# NU-Smarticles.net
KiCad netlist of a schematic drawn in EAGLE
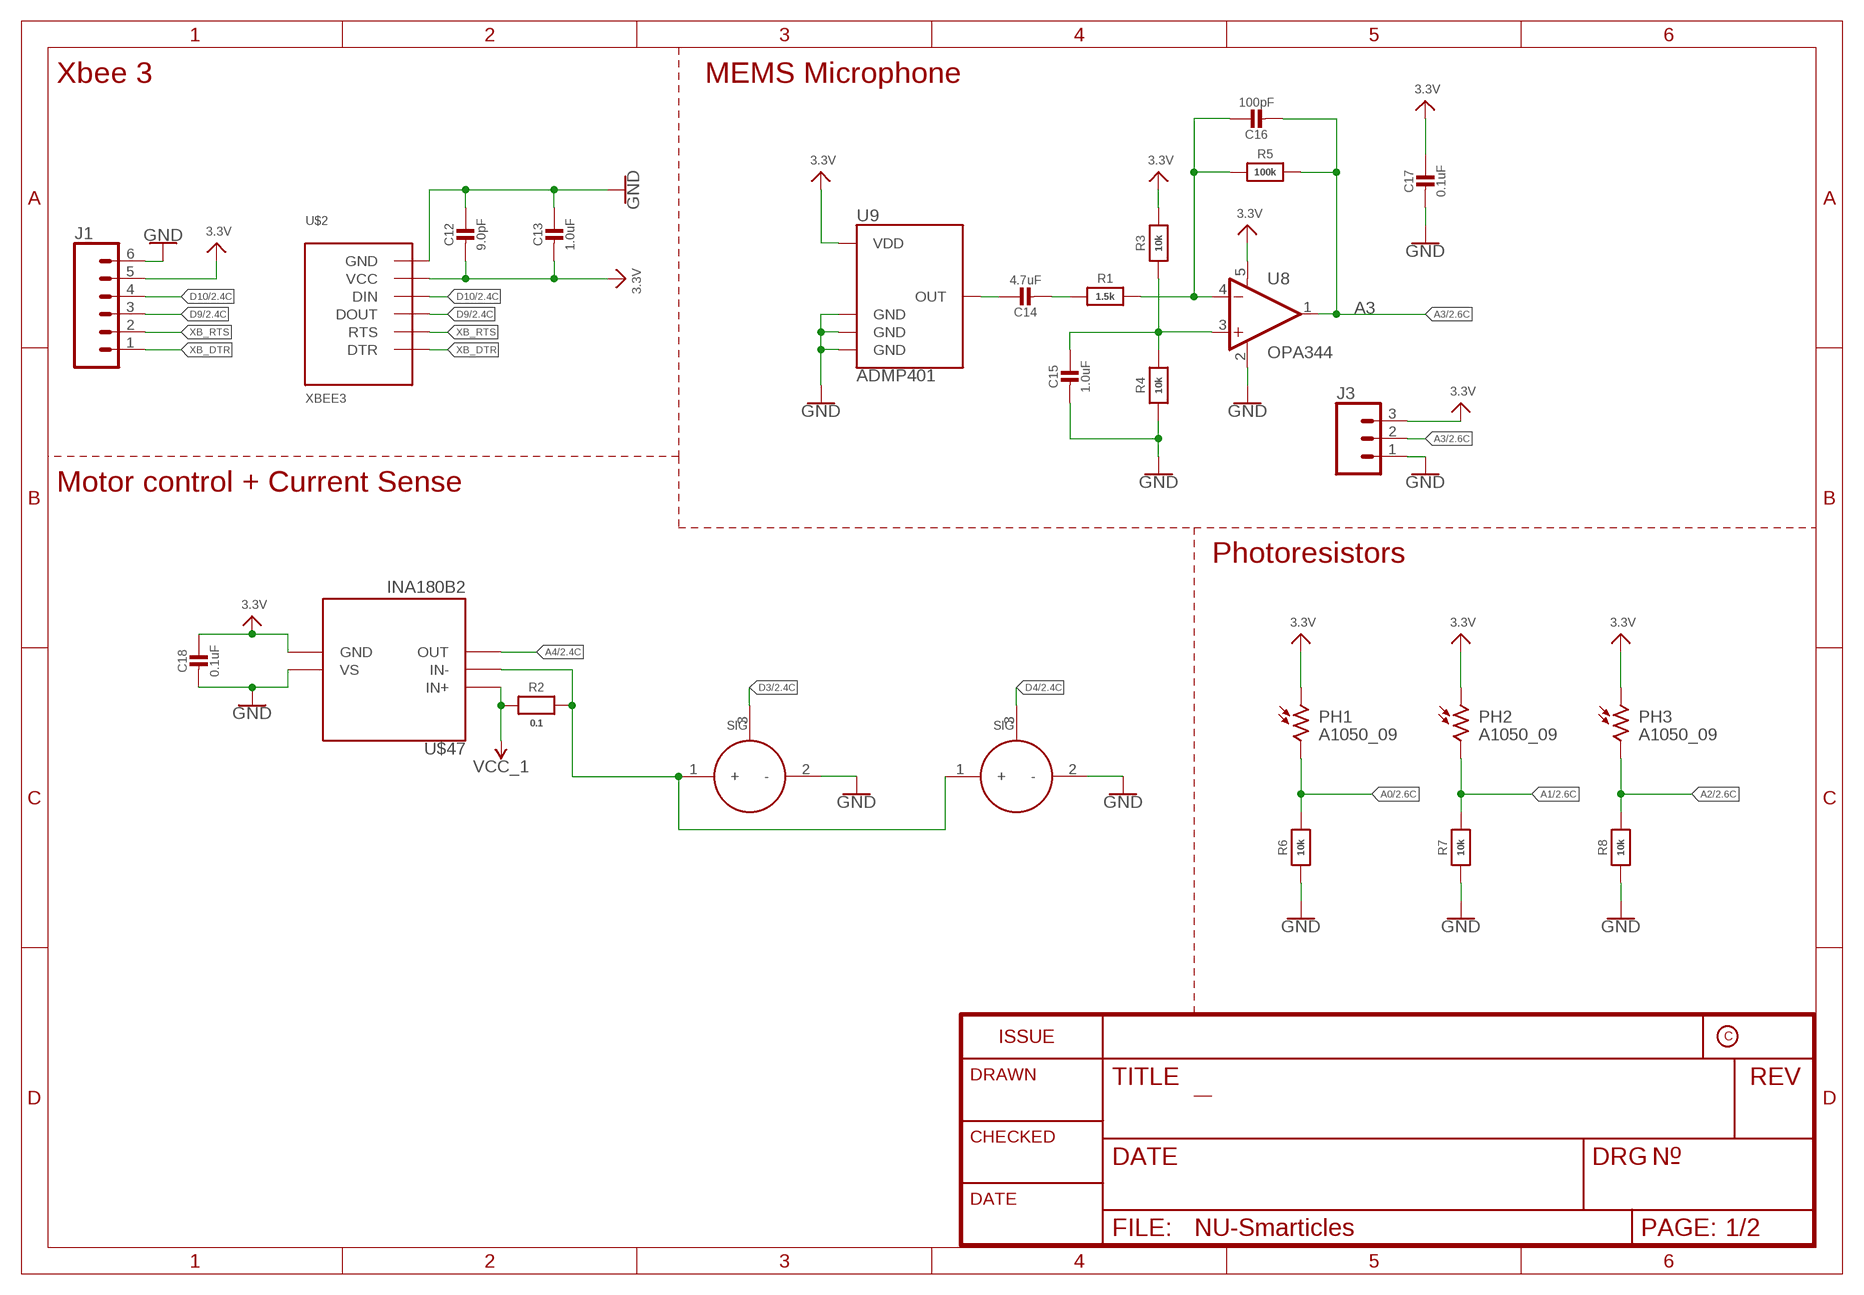
[diagram p0: schematic, sheet 1]
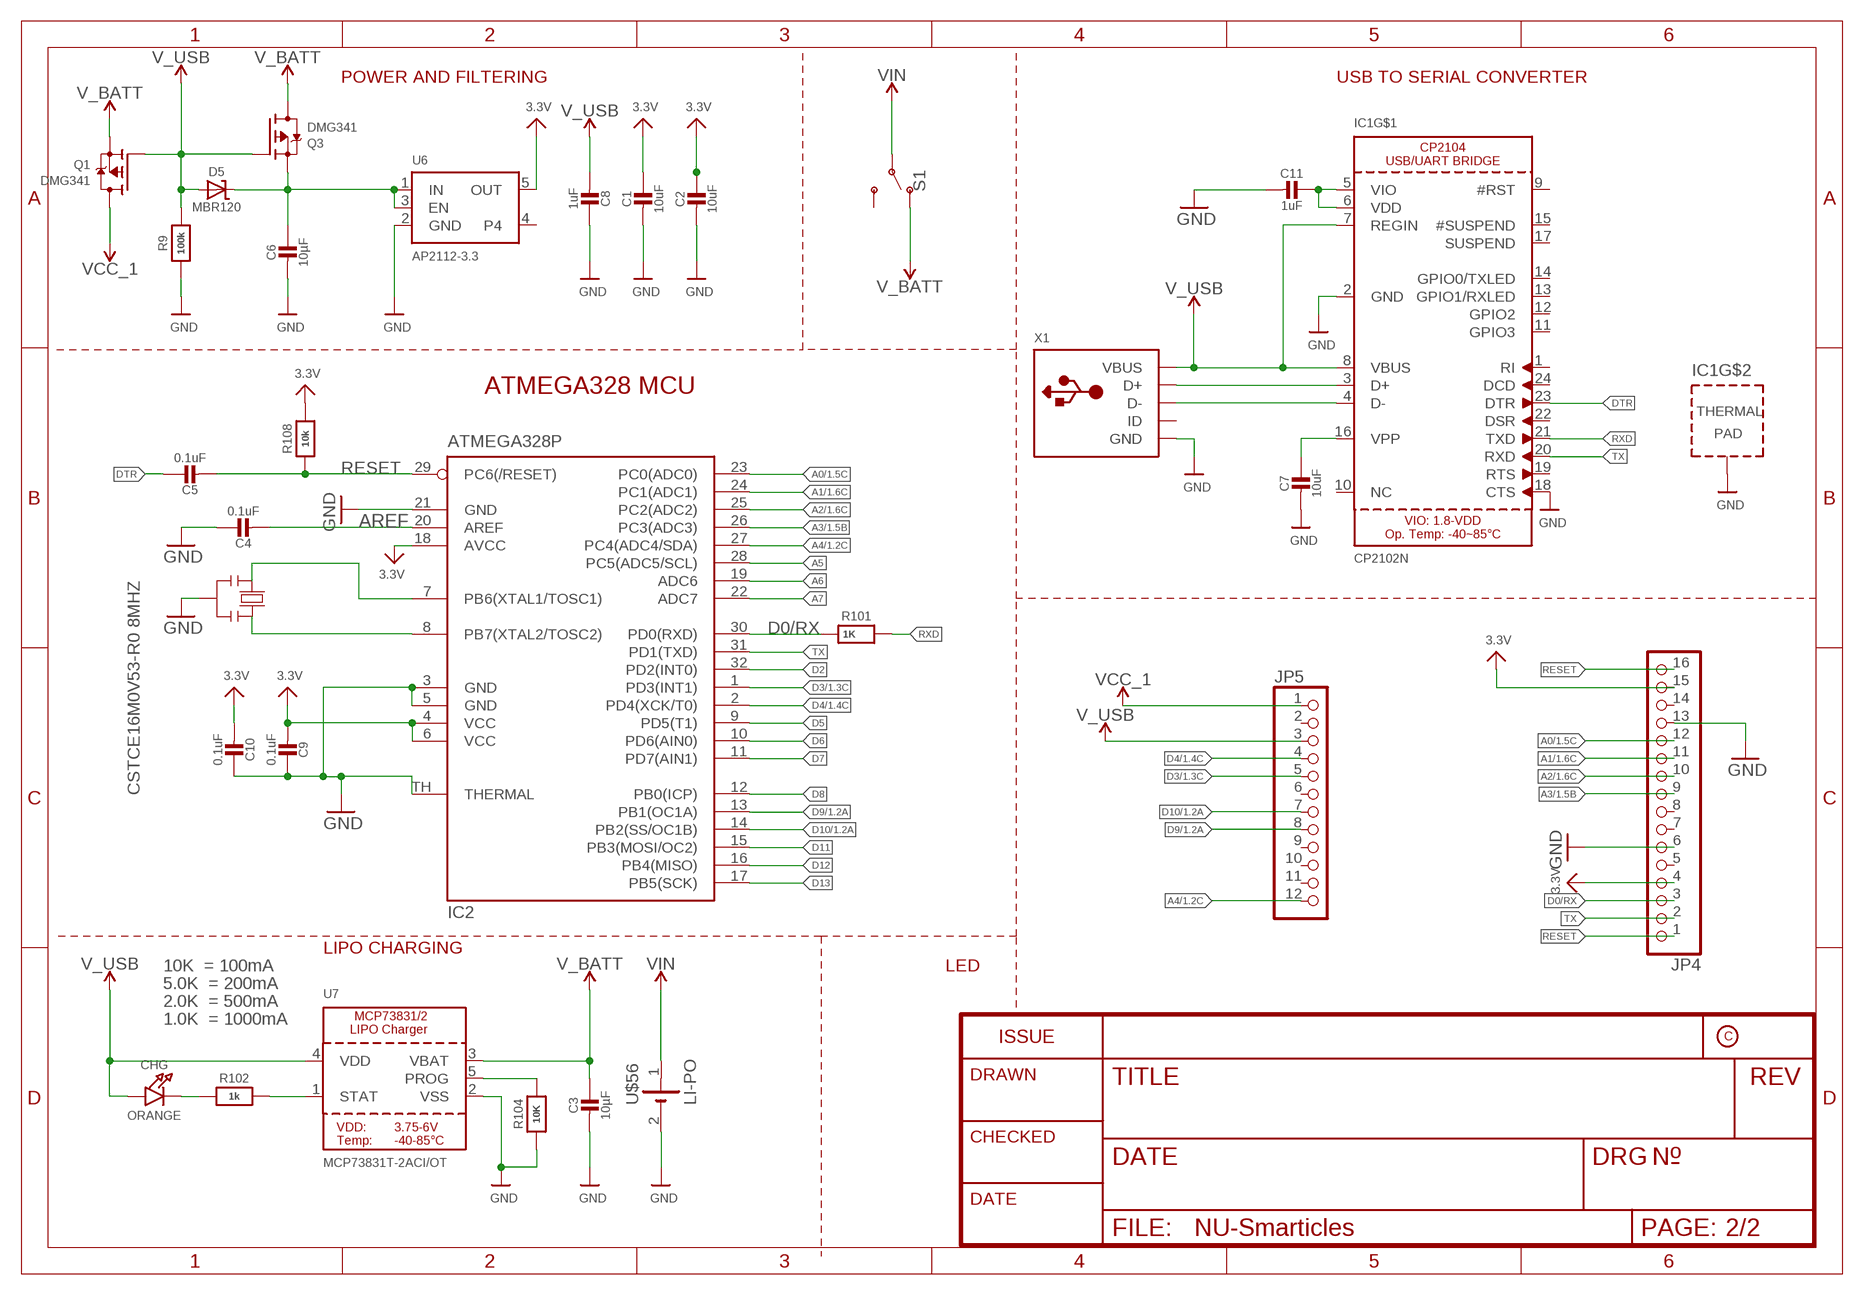
[diagram p1: schematic, sheet 2]

(export (version "E")
  (design (tool "Eeschema 10.0.6"))
  (components
    (comp (ref "C1")
      (value "10uF")
      (footprint "eagle-import:_0402MP")
      (libsource (lib "eagle-import") (part "CAP_CERAMIC_0402MP"))
    )
    (comp (ref "C2")
      (value "10uF")
      (footprint "eagle-import:_0402MP")
      (libsource (lib "eagle-import") (part "CAP_CERAMIC_0402MP"))
    )
    (comp (ref "C3")
      (value "10µF")
      (footprint "eagle-import:_0402MP")
      (libsource (lib "eagle-import") (part "microbuilder_CAP_CERAMIC_0402MP"))
    )
    (comp (ref "C4")
      (value "0.1uF")
      (footprint "eagle-import:_0402MP")
      (libsource (lib "eagle-import") (part "CAP_CERAMIC_0402MP"))
    )
    (comp (ref "C5")
      (value "0.1uF")
      (footprint "eagle-import:_0402MP")
      (libsource (lib "eagle-import") (part "CAP_CERAMIC_0402MP"))
    )
    (comp (ref "C6")
      (value "10µF")
      (footprint "eagle-import:_0402MP")
      (libsource (lib "eagle-import") (part "CAP_CERAMIC_0402MP"))
    )
    (comp (ref "C7")
      (value "10uF")
      (footprint "eagle-import:_0402MP")
      (libsource (lib "eagle-import") (part "CAP_CERAMIC_0402MP"))
    )
    (comp (ref "C8")
      (value "1uF")
      (footprint "eagle-import:_0402MP")
      (libsource (lib "eagle-import") (part "CAP_CERAMIC_0402MP"))
    )
    (comp (ref "C9")
      (value "0.1uF")
      (footprint "eagle-import:_0402MP")
      (libsource (lib "eagle-import") (part "CAP_CERAMIC_0402MP"))
    )
    (comp (ref "C10")
      (value "0.1uF")
      (footprint "eagle-import:_0402MP")
      (libsource (lib "eagle-import") (part "CAP_CERAMIC_0402MP"))
    )
    (comp (ref "C11")
      (value "1uF")
      (footprint "eagle-import:_0402MP")
      (libsource (lib "eagle-import") (part "CAP_CERAMIC_0402MP"))
    )
    (comp (ref "CHG")
      (value "ORANGE")
      (footprint "eagle-import:CHIPLED_0603")
      (libsource (lib "eagle-import") (part "LED0603"))
    )
    (comp (ref "D5")
      (value "MBR120")
      (footprint "eagle-import:SOD-523")
      (libsource (lib "eagle-import") (part "DIODE-SCHOTTKYSOD-523"))
    )
    (comp (ref "IC1")
      (value "CP2102N")
      (footprint "eagle-import:QFN24_4MM_SMSC")
      (libsource (lib "eagle-import") (part "CP2104"))
    )
    (comp (ref "IC2")
      (value "ATMEGA328P")
      (footprint "eagle-import:MLF32-TH")
      (fields (field (name "MPN") "ATMEGA88PA-MU"))
      (libsource (lib "eagle-import") (part "MEGA8-MI"))
    )
    (comp (ref "JP4")
      (value "HEADER-1X16ROUND")
      (footprint "eagle-import:1X16_ROUND")
      (libsource (lib "eagle-import") (part "HEADER-1X16ROUND"))
    )
    (comp (ref "JP5")
      (value "HEADER-1X12")
      (footprint "eagle-import:1X12_ROUND")
      (libsource (lib "eagle-import") (part "HEADER-1X12"))
    )
    (comp (ref "Q1")
      (value "DMG341")
      (footprint "eagle-import:SOT23-R")
      (libsource (lib "eagle-import") (part "MOSFET-P"))
    )
    (comp (ref "Q3")
      (value "DMG341")
      (footprint "eagle-import:SOT23-R")
      (libsource (lib "eagle-import") (part "MOSFET-P"))
    )
    (comp (ref "R9")
      (value "100k")
      (footprint "eagle-import:_0402MP")
      (libsource (lib "eagle-import") (part "RESISTOR_0402MP"))
    )
    (comp (ref "R101")
      (value "1K")
      (footprint "eagle-import:_0402MP")
      (libsource (lib "eagle-import") (part "microbuilder_RESISTOR_0402MP"))
    )
    (comp (ref "R102")
      (value "1k")
      (footprint "eagle-import:_0402MP")
      (libsource (lib "eagle-import") (part "RESISTOR_0402MP"))
    )
    (comp (ref "R104")
      (value "10K")
      (footprint "eagle-import:_0402MP")
      (libsource (lib "eagle-import") (part "microbuilder_RESISTOR_0402MP"))
    )
    (comp (ref "R108")
      (value "10k")
      (footprint "eagle-import:_0402MP")
      (libsource (lib "eagle-import") (part "RESISTOR_0402MP"))
    )
    (comp (ref "S1")
      (value "SWITCH-SPDT-SMD-AYZ0202")
      (footprint "eagle-import:SWITCH_DPDT_SMD_AYZ0202")
      (libsource (lib "eagle-import") (part "SWITCH-SPDT-SMD-AYZ0202"))
    )
    (comp (ref "U$56")
      (value "LI-PO")
      (footprint "eagle-import:1X02_BATT")
      (libsource (lib "eagle-import") (part "LI-PO"))
    )
    (comp (ref "U6")
      (value "AP2112-3.3")
      (footprint "eagle-import:SOT23-5")
      (libsource (lib "eagle-import") (part "VREG_SOT23-5"))
    )
    (comp (ref "U7")
      (value "MCP73831T-2ACI/OT")
      (footprint "eagle-import:SOT23-5")
      (libsource (lib "eagle-import") (part "MCP73831/2"))
    )
    (comp (ref "X1")
      (value "USBMICRO_20329")
      (footprint "eagle-import:4UCONN_20329")
      (libsource (lib "eagle-import") (part "USBMICRO_20329"))
    )
    (comp (ref "Y2")
      (value "CSTCE16M0V53-R0 8MHZ")
      (footprint "eagle-import:RESONATOR")
      (libsource (lib "eagle-import") (part "RESONATORMU"))
    )
    (comp (ref "C12")
      (value "9.0pF")
      (footprint "eagle-import:_0402MP")
      (libsource (lib "eagle-import") (part "CAP_CERAMIC_0402MP"))
    )
    (comp (ref "C13")
      (value "1.0uF")
      (footprint "eagle-import:_0402MP")
      (libsource (lib "eagle-import") (part "CAP_CERAMIC_0402MP"))
    )
    (comp (ref "C14")
      (value "4.7uF")
      (footprint "eagle-import:_0402MP")
      (libsource (lib "eagle-import") (part "CAP_CERAMIC_0402MP"))
    )
    (comp (ref "C15")
      (value "1.0uF")
      (footprint "eagle-import:_0402MP")
      (libsource (lib "eagle-import") (part "CAP_CERAMIC_0402MP"))
    )
    (comp (ref "C16")
      (value "100pF")
      (footprint "eagle-import:_0402MP")
      (libsource (lib "eagle-import") (part "CAP_CERAMIC_0402MP"))
    )
    (comp (ref "C17")
      (value "0.1uF")
      (footprint "eagle-import:_0402MP")
      (libsource (lib "eagle-import") (part "CAP_CERAMIC_0402MP"))
    )
    (comp (ref "C18")
      (value "0.1uF")
      (footprint "eagle-import:_0402MP")
      (libsource (lib "eagle-import") (part "CAP_CERAMIC_0402MP"))
    )
    (comp (ref "J1")
      (value "CONN_06NO_SILK_FEMALE_PTH")
      (footprint "eagle-import:1X06_NO_SILK")
      (libsource (lib "eagle-import") (part "CONN_06NO_SILK_FEMALE_PTH"))
    )
    (comp (ref "J3")
      (value "CONN_03")
      (footprint "eagle-import:1X03")
      (libsource (lib "eagle-import") (part "CONN_03"))
    )
    (comp (ref "PH1")
      (value "A1050_09")
      (footprint "eagle-import:T0-46-A10XX")
      (libsource (lib "eagle-import") (part "A1050_09"))
    )
    (comp (ref "PH2")
      (value "A1050_09")
      (footprint "eagle-import:T0-46-A10XX")
      (libsource (lib "eagle-import") (part "A1050_09"))
    )
    (comp (ref "PH3")
      (value "A1050_09")
      (footprint "eagle-import:T0-46-A10XX")
      (libsource (lib "eagle-import") (part "A1050_09"))
    )
    (comp (ref "R1")
      (value "1.5k")
      (footprint "eagle-import:_0402MP")
      (libsource (lib "eagle-import") (part "RESISTOR_0402MP"))
    )
    (comp (ref "R2")
      (value "0.1")
      (footprint "eagle-import:_0603MP")
      (libsource (lib "eagle-import") (part "RESISTOR_0603MP"))
    )
    (comp (ref "R3")
      (value "10k")
      (footprint "eagle-import:_0402MP")
      (libsource (lib "eagle-import") (part "RESISTOR_0402MP"))
    )
    (comp (ref "R4")
      (value "10k")
      (footprint "eagle-import:_0402MP")
      (libsource (lib "eagle-import") (part "RESISTOR_0402MP"))
    )
    (comp (ref "R5")
      (value "100k")
      (footprint "eagle-import:_0402MP")
      (libsource (lib "eagle-import") (part "RESISTOR_0402MP"))
    )
    (comp (ref "R6")
      (value "10k")
      (footprint "eagle-import:_0402MP")
      (libsource (lib "eagle-import") (part "RESISTOR_0402MP"))
    )
    (comp (ref "R7")
      (value "10k")
      (footprint "eagle-import:_0402MP")
      (libsource (lib "eagle-import") (part "RESISTOR_0402MP"))
    )
    (comp (ref "R8")
      (value "10k")
      (footprint "eagle-import:_0402MP")
      (libsource (lib "eagle-import") (part "RESISTOR_0402MP"))
    )
    (comp (ref "U$1")
      (value "SERVO")
      (footprint "eagle-import:1X03_SERVO")
      (libsource (lib "eagle-import") (part "SERVO"))
    )
    (comp (ref "U$2")
      (value "XBEE3")
      (footprint "eagle-import:XBEE3_MICRO")
      (libsource (lib "eagle-import") (part "XBEE3"))
    )
    (comp (ref "U$46")
      (value "SERVO")
      (footprint "eagle-import:1X03_SERVO")
      (libsource (lib "eagle-import") (part "SERVO"))
    )
    (comp (ref "U$47")
      (value "INA180B2")
      (footprint "eagle-import:SOT23-5")
      (libsource (lib "eagle-import") (part "INA180B2"))
    )
    (comp (ref "U8")
      (value "OPA344")
      (footprint "eagle-import:SOT23-5")
      (libsource (lib "eagle-import") (part "OPA344"))
    )
    (comp (ref "U9")
      (value "ADMP401")
      (footprint "eagle-import:ADMP401")
      (libsource (lib "eagle-import") (part "ADMP401"))
    )
  )
  (nets
    (net (code "1") (name "3.3V") (class "Default")
      (node (ref "C1") (pin "1") (pinfunction "1_1") (pintype "passive"))
      (node (ref "C10") (pin "2") (pinfunction "2_2") (pintype "passive"))
      (node (ref "C12") (pin "2") (pinfunction "2_2") (pintype "passive"))
      (node (ref "C13") (pin "2") (pinfunction "2_2") (pintype "passive"))
      (node (ref "C17") (pin "1") (pinfunction "1_1") (pintype "passive"))
      (node (ref "C18") (pin "1") (pinfunction "1_1") (pintype "passive"))
      (node (ref "C2") (pin "1") (pinfunction "1_1") (pintype "passive"))
      (node (ref "C9") (pin "2") (pinfunction "2_2") (pintype "passive"))
      (node (ref "IC2") (pin "18") (pinfunction "AVCC_18") (pintype "power_in"))
      (node (ref "IC2") (pin "4") (pinfunction "VCC_4") (pintype "power_in"))
      (node (ref "IC2") (pin "6") (pinfunction "VCC_6") (pintype "power_in"))
      (node (ref "J1") (pin "5") (pinfunction "5_5") (pintype "passive"))
      (node (ref "J3") (pin "3") (pinfunction "3_3") (pintype "passive"))
      (node (ref "JP4") (pin "15") (pinfunction "15_15") (pintype "passive"))
      (node (ref "JP4") (pin "4") (pinfunction "4_4") (pintype "passive"))
      (node (ref "PH1") (pin "1") (pinfunction "1_1") (pintype "passive"))
      (node (ref "PH2") (pin "1") (pinfunction "1_1") (pintype "passive"))
      (node (ref "PH3") (pin "1") (pinfunction "1_1") (pintype "passive"))
      (node (ref "R108") (pin "2") (pinfunction "2_2") (pintype "passive"))
      (node (ref "R3") (pin "2") (pinfunction "2_2") (pintype "passive"))
      (node (ref "U$2") (pin "VCC") (pinfunction "VCC_VCC") (pintype "bidirectional"))
      (node (ref "U$47") (pin "2") (pinfunction "GND_2") (pintype "bidirectional"))
      (node (ref "U6") (pin "5") (pinfunction "OUT_5") (pintype "power_in"))
      (node (ref "U8") (pin "5") (pinfunction "V+_5") (pintype "power_in"))
      (node (ref "U9") (pin "5") (pinfunction "VDD_5") (pintype "bidirectional"))
    )
    (net (code "2") (name "A0") (class "Default")
      (node (ref "IC2") (pin "23") (pinfunction "PC0(ADC0)_23") (pintype "bidirectional"))
      (node (ref "JP4") (pin "12") (pinfunction "12_12") (pintype "passive"))
      (node (ref "PH1") (pin "2") (pinfunction "2_2") (pintype "passive"))
      (node (ref "R6") (pin "2") (pinfunction "2_2") (pintype "passive"))
    )
    (net (code "3") (name "A1") (class "Default")
      (node (ref "IC2") (pin "24") (pinfunction "PC1(ADC1)_24") (pintype "bidirectional"))
      (node (ref "JP4") (pin "11") (pinfunction "11_11") (pintype "passive"))
      (node (ref "PH2") (pin "2") (pinfunction "2_2") (pintype "passive"))
      (node (ref "R7") (pin "2") (pinfunction "2_2") (pintype "passive"))
    )
    (net (code "4") (name "A2") (class "Default")
      (node (ref "IC2") (pin "25") (pinfunction "PC2(ADC2)_25") (pintype "bidirectional"))
      (node (ref "JP4") (pin "10") (pinfunction "10_10") (pintype "passive"))
      (node (ref "PH3") (pin "2") (pinfunction "2_2") (pintype "passive"))
      (node (ref "R8") (pin "2") (pinfunction "2_2") (pintype "passive"))
    )
    (net (code "5") (name "A3") (class "Default")
      (node (ref "C16") (pin "2") (pinfunction "2_2") (pintype "passive"))
      (node (ref "IC2") (pin "26") (pinfunction "PC3(ADC3)_26") (pintype "bidirectional"))
      (node (ref "J3") (pin "2") (pinfunction "2_2") (pintype "passive"))
      (node (ref "JP4") (pin "9") (pinfunction "9_9") (pintype "passive"))
      (node (ref "R5") (pin "2") (pinfunction "2_2") (pintype "passive"))
      (node (ref "U8") (pin "1") (pinfunction "OUT_1") (pintype "output"))
    )
    (net (code "6") (name "A4") (class "Default")
      (node (ref "IC2") (pin "27") (pinfunction "PC4(ADC4/SDA)_27") (pintype "bidirectional"))
      (node (ref "JP5") (pin "12") (pinfunction "12_12") (pintype "passive"))
      (node (ref "U$47") (pin "4") (pinfunction "OUT_4") (pintype "bidirectional"))
    )
    (net (code "7") (name "A5") (class "Default")
      (node (ref "IC2") (pin "28") (pinfunction "PC5(ADC5/SCL)_28") (pintype "bidirectional"))
    )
    (net (code "8") (name "A6") (class "Default")
      (node (ref "IC2") (pin "19") (pinfunction "ADC6_19") (pintype "bidirectional"))
    )
    (net (code "9") (name "A7") (class "Default")
      (node (ref "IC2") (pin "22") (pinfunction "ADC7_22") (pintype "bidirectional"))
    )
    (net (code "10") (name "AREF") (class "Default")
      (node (ref "C4") (pin "2") (pinfunction "2_2") (pintype "passive"))
      (node (ref "IC2") (pin "20") (pinfunction "AREF_20") (pintype "passive"))
    )
    (net (code "11") (name "D0{slash}RX") (class "Default")
      (node (ref "IC2") (pin "30") (pinfunction "PD0(RXD)_30") (pintype "bidirectional"))
      (node (ref "JP4") (pin "3") (pinfunction "3_3") (pintype "passive"))
      (node (ref "R101") (pin "1") (pinfunction "1_1") (pintype "passive"))
    )
    (net (code "12") (name "D2") (class "Default")
      (node (ref "IC2") (pin "32") (pinfunction "PD2(INT0)_32") (pintype "bidirectional"))
    )
    (net (code "13") (name "D3") (class "Default")
      (node (ref "IC2") (pin "1") (pinfunction "PD3(INT1)_1") (pintype "bidirectional"))
      (node (ref "JP5") (pin "5") (pinfunction "5_5") (pintype "passive"))
      (node (ref "U$1") (pin "3") (pinfunction "SIG_3") (pintype "bidirectional"))
    )
    (net (code "14") (name "D4") (class "Default")
      (node (ref "IC2") (pin "2") (pinfunction "PD4(XCK/T0)_2") (pintype "bidirectional"))
      (node (ref "JP5") (pin "4") (pinfunction "4_4") (pintype "passive"))
      (node (ref "U$46") (pin "3") (pinfunction "SIG_3") (pintype "bidirectional"))
    )
    (net (code "15") (name "D5") (class "Default")
      (node (ref "IC2") (pin "9") (pinfunction "PD5(T1)_9") (pintype "bidirectional"))
    )
    (net (code "16") (name "D6") (class "Default")
      (node (ref "IC2") (pin "10") (pinfunction "PD6(AIN0)_10") (pintype "bidirectional"))
    )
    (net (code "17") (name "D7") (class "Default")
      (node (ref "IC2") (pin "11") (pinfunction "PD7(AIN1)_11") (pintype "bidirectional"))
    )
    (net (code "18") (name "D8") (class "Default")
      (node (ref "IC2") (pin "12") (pinfunction "PB0(ICP)_12") (pintype "bidirectional"))
    )
    (net (code "19") (name "D9") (class "Default")
      (node (ref "IC2") (pin "13") (pinfunction "PB1(OC1A)_13") (pintype "bidirectional"))
      (node (ref "J1") (pin "3") (pinfunction "3_3") (pintype "passive"))
      (node (ref "JP5") (pin "8") (pinfunction "8_8") (pintype "passive"))
      (node (ref "U$2") (pin "DOUT/DIO13") (pinfunction "DOUT_DOUT/DIO13") (pintype "bidirectional"))
    )
    (net (code "20") (name "D10") (class "Default")
      (node (ref "IC2") (pin "14") (pinfunction "PB2(SS/OC1B)_14") (pintype "bidirectional"))
      (node (ref "J1") (pin "4") (pinfunction "4_4") (pintype "passive"))
      (node (ref "JP5") (pin "7") (pinfunction "7_7") (pintype "passive"))
      (node (ref "U$2") (pin "DIN/CONFIG/DIO14") (pinfunction "DIN_DIN/CONFIG/DIO14") (pintype "bidirectional"))
    )
    (net (code "21") (name "D11") (class "Default")
      (node (ref "IC2") (pin "15") (pinfunction "PB3(MOSI/OC2)_15") (pintype "bidirectional"))
    )
    (net (code "22") (name "D12") (class "Default")
      (node (ref "IC2") (pin "16") (pinfunction "PB4(MISO)_16") (pintype "bidirectional"))
    )
    (net (code "23") (name "D13") (class "Default")
      (node (ref "IC2") (pin "17") (pinfunction "PB5(SCK)_17") (pintype "bidirectional"))
    )
    (net (code "24") (name "DTR") (class "Default")
      (node (ref "C5") (pin "1") (pinfunction "1_1") (pintype "passive"))
      (node (ref "IC1") (pin "23") (pinfunction "DTR_23") (pintype "output"))
    )
    (net (code "25") (name "GND") (class "Default")
      (node (ref "C1") (pin "2") (pinfunction "2_2") (pintype "passive"))
      (node (ref "C10") (pin "1") (pinfunction "1_1") (pintype "passive"))
      (node (ref "C11") (pin "2") (pinfunction "2_2") (pintype "passive"))
      (node (ref "C12") (pin "1") (pinfunction "1_1") (pintype "passive"))
      (node (ref "C13") (pin "1") (pinfunction "1_1") (pintype "passive"))
      (node (ref "C15") (pin "2") (pinfunction "2_2") (pintype "passive"))
      (node (ref "C17") (pin "2") (pinfunction "2_2") (pintype "passive"))
      (node (ref "C18") (pin "2") (pinfunction "2_2") (pintype "passive"))
      (node (ref "C2") (pin "2") (pinfunction "2_2") (pintype "passive"))
      (node (ref "C3") (pin "2") (pinfunction "2_2") (pintype "passive"))
      (node (ref "C4") (pin "1") (pinfunction "1_1") (pintype "passive"))
      (node (ref "C6") (pin "2") (pinfunction "2_2") (pintype "passive"))
      (node (ref "C7") (pin "2") (pinfunction "2_2") (pintype "passive"))
      (node (ref "C8") (pin "1") (pinfunction "1_1") (pintype "passive"))
      (node (ref "C9") (pin "1") (pinfunction "1_1") (pintype "passive"))
      (node (ref "IC1") (pin "18") (pinfunction "CTS_18") (pintype "input"))
      (node (ref "IC1") (pin "2") (pinfunction "GND_2") (pintype "power_in"))
      (node (ref "IC1") (pin "THERM") (pinfunction "TP_THERM") (pintype "power_in"))
      (node (ref "IC2") (pin "21") (pinfunction "GND_21") (pintype "power_in"))
      (node (ref "IC2") (pin "3") (pinfunction "GND_3") (pintype "power_in"))
      (node (ref "IC2") (pin "5") (pinfunction "GND_5") (pintype "power_in"))
      (node (ref "IC2") (pin "TH") (pinfunction "THERMAL_TH") (pintype "passive"))
      (node (ref "J1") (pin "6") (pinfunction "6_6") (pintype "passive"))
      (node (ref "J3") (pin "1") (pinfunction "1_1") (pintype "passive"))
      (node (ref "JP4") (pin "13") (pinfunction "13_13") (pintype "passive"))
      (node (ref "JP4") (pin "6") (pinfunction "6_6") (pintype "passive"))
      (node (ref "R104") (pin "1") (pinfunction "1_1") (pintype "passive"))
      (node (ref "R4") (pin "1") (pinfunction "1_1") (pintype "passive"))
      (node (ref "R6") (pin "1") (pinfunction "1_1") (pintype "passive"))
      (node (ref "R7") (pin "1") (pinfunction "1_1") (pintype "passive"))
      (node (ref "R8") (pin "1") (pinfunction "1_1") (pintype "passive"))
      (node (ref "R9") (pin "1") (pinfunction "1_1") (pintype "passive"))
      (node (ref "U$1") (pin "2") (pinfunction "-_2") (pintype "bidirectional"))
      (node (ref "U$2") (pin "GND1") (pinfunction "GND_GND1") (pintype "bidirectional"))
      (node (ref "U$46") (pin "2") (pinfunction "-_2") (pintype "bidirectional"))
      (node (ref "U$47") (pin "5") (pinfunction "VS_5") (pintype "bidirectional"))
      (node (ref "U$56") (pin "2") (pinfunction "-_2") (pintype "passive"))
      (node (ref "U6") (pin "2") (pinfunction "GND_2") (pintype "power_in"))
      (node (ref "U7") (pin "2") (pinfunction "VSS_2") (pintype "power_in"))
      (node (ref "U8") (pin "2") (pinfunction "V-_2") (pintype "power_in"))
      (node (ref "U9") (pin "2") (pinfunction "GND_2") (pintype "bidirectional"))
      (node (ref "U9") (pin "4") (pinfunction "GND_4") (pintype "bidirectional"))
      (node (ref "U9") (pin "6") (pinfunction "GND_6") (pintype "bidirectional"))
      (node (ref "X1") (pin "BASE@1") (pinfunction "GND_BASE@1") (pintype "power_in"))
      (node (ref "X1") (pin "BASE@2") (pinfunction "GND_BASE@2") (pintype "power_in"))
      (node (ref "X1") (pin "GND") (pinfunction "GND_GND") (pintype "power_in"))
      (node (ref "X1") (pin "SPRT@1") (pinfunction "GND_SPRT@1") (pintype "power_in"))
      (node (ref "X1") (pin "SPRT@2") (pinfunction "GND_SPRT@2") (pintype "power_in"))
      (node (ref "X1") (pin "SPRT@3") (pinfunction "GND_SPRT@3") (pintype "power_in"))
      (node (ref "X1") (pin "SPRT@4") (pinfunction "GND_SPRT@4") (pintype "power_in"))
      (node (ref "Y2") (pin "2") (pinfunction "2_2") (pintype "passive"))
    )
    (net (code "26") (name "Net-(C14-Pad2)") (class "Default")
      (node (ref "C14") (pin "2") (pinfunction "2_2") (pintype "passive"))
      (node (ref "R1") (pin "1") (pinfunction "1_1") (pintype "passive"))
    )
    (net (code "27") (name "Net-(CHG-PadC)") (class "Default")
      (node (ref "CHG") (pin "C") (pinfunction "C_C") (pintype "passive"))
      (node (ref "R102") (pin "1") (pinfunction "1_1") (pintype "passive"))
    )
    (net (code "28") (name "Net-(D5-C)") (class "Default")
      (node (ref "C6") (pin "1") (pinfunction "1_1") (pintype "passive"))
      (node (ref "D5") (pin "K") (pinfunction "C_K") (pintype "passive"))
      (node (ref "Q3") (pin "2") (pinfunction "S_2") (pintype "passive"))
      (node (ref "U6") (pin "1") (pinfunction "IN_1") (pintype "power_in"))
      (node (ref "U6") (pin "3") (pinfunction "EN_3") (pintype "input"))
    )
    (net (code "29") (name "Net-(IC1A-D+)") (class "Default")
      (node (ref "IC1") (pin "3") (pinfunction "D+_3") (pintype "bidirectional"))
      (node (ref "X1") (pin "D+") (pinfunction "D+_D+") (pintype "bidirectional"))
    )
    (net (code "30") (name "Net-(IC1A-D-)") (class "Default")
      (node (ref "IC1") (pin "4") (pinfunction "D-_4") (pintype "bidirectional"))
      (node (ref "X1") (pin "D-") (pinfunction "D-_D-") (pintype "bidirectional"))
    )
    (net (code "31") (name "Net-(IC1A-VDD)") (class "Default")
      (node (ref "C11") (pin "1") (pinfunction "1_1") (pintype "passive"))
      (node (ref "IC1") (pin "5") (pinfunction "VIO_5") (pintype "power_in"))
      (node (ref "IC1") (pin "6") (pinfunction "VDD_6") (pintype "power_in"))
    )
    (net (code "32") (name "Net-(IC1A-VPP)") (class "Default")
      (node (ref "C7") (pin "1") (pinfunction "1_1") (pintype "passive"))
      (node (ref "IC1") (pin "16") (pinfunction "VPP_16") (pintype "bidirectional"))
    )
    (net (code "33") (name "Net-(IC2-PB6(XTAL1{slash}TOSC1))") (class "Default")
      (node (ref "IC2") (pin "7") (pinfunction "PB6(XTAL1/TOSC1)_7") (pintype "bidirectional"))
      (node (ref "Y2") (pin "1") (pinfunction "1_1") (pintype "passive"))
    )
    (net (code "34") (name "Net-(IC2-PB7(XTAL2{slash}TOSC2))") (class "Default")
      (node (ref "IC2") (pin "8") (pinfunction "PB7(XTAL2/TOSC2)_8") (pintype "bidirectional"))
      (node (ref "Y2") (pin "3") (pinfunction "3_3") (pintype "passive"))
    )
    (net (code "35") (name "Net-(U$1-+)") (class "Default")
      (node (ref "R2") (pin "2") (pinfunction "2_2") (pintype "passive"))
      (node (ref "U$1") (pin "1") (pinfunction "+_1") (pintype "bidirectional"))
      (node (ref "U$46") (pin "1") (pinfunction "+_1") (pintype "bidirectional"))
      (node (ref "U$47") (pin "3") (pinfunction "IN-_3") (pintype "bidirectional"))
    )
    (net (code "36") (name "Net-(U7-PROG)") (class "Default")
      (node (ref "R104") (pin "2") (pinfunction "2_2") (pintype "passive"))
      (node (ref "U7") (pin "5") (pinfunction "PROG_5") (pintype "input"))
    )
    (net (code "37") (name "Net-(U7-STAT)") (class "Default")
      (node (ref "R102") (pin "2") (pinfunction "2_2") (pintype "passive"))
      (node (ref "U7") (pin "1") (pinfunction "STAT_1") (pintype "output"))
    )
    (net (code "38") (name "Net-(U8-+IN)") (class "Default")
      (node (ref "C15") (pin "1") (pinfunction "1_1") (pintype "passive"))
      (node (ref "R3") (pin "1") (pinfunction "1_1") (pintype "passive"))
      (node (ref "R4") (pin "2") (pinfunction "2_2") (pintype "passive"))
      (node (ref "U8") (pin "3") (pinfunction "+IN_3") (pintype "input"))
    )
    (net (code "39") (name "Net-(U8--IN)") (class "Default")
      (node (ref "C16") (pin "1") (pinfunction "1_1") (pintype "passive"))
      (node (ref "R1") (pin "2") (pinfunction "2_2") (pintype "passive"))
      (node (ref "R5") (pin "1") (pinfunction "1_1") (pintype "passive"))
      (node (ref "U8") (pin "4") (pinfunction "-IN_4") (pintype "input"))
    )
    (net (code "40") (name "Net-(U9-OUT)") (class "Default")
      (node (ref "C14") (pin "1") (pinfunction "1_1") (pintype "passive"))
      (node (ref "U9") (pin "1") (pinfunction "OUT_1") (pintype "bidirectional"))
    )
    (net (code "41") (name "RESET") (class "Default")
      (node (ref "C5") (pin "2") (pinfunction "2_2") (pintype "passive"))
      (node (ref "IC2") (pin "29") (pinfunction "PC6(/RESET)_29") (pintype "bidirectional"))
      (node (ref "JP4") (pin "1") (pinfunction "1_1") (pintype "passive"))
      (node (ref "JP4") (pin "16") (pinfunction "16_16") (pintype "passive"))
      (node (ref "R108") (pin "1") (pinfunction "1_1") (pintype "passive"))
    )
    (net (code "42") (name "RXD") (class "Default")
      (node (ref "IC1") (pin "21") (pinfunction "TXD_21") (pintype "output"))
      (node (ref "R101") (pin "2") (pinfunction "2_2") (pintype "passive"))
    )
    (net (code "43") (name "TX") (class "Default")
      (node (ref "IC1") (pin "20") (pinfunction "RXD_20") (pintype "input"))
      (node (ref "IC2") (pin "31") (pinfunction "PD1(TXD)_31") (pintype "bidirectional"))
      (node (ref "JP4") (pin "2") (pinfunction "2_2") (pintype "passive"))
    )
    (net (code "44") (name "VCC_1") (class "Default")
      (node (ref "JP5") (pin "1") (pinfunction "1_1") (pintype "passive"))
      (node (ref "Q1") (pin "3") (pinfunction "D_3") (pintype "passive"))
      (node (ref "R2") (pin "1") (pinfunction "1_1") (pintype "passive"))
      (node (ref "U$47") (pin "1") (pinfunction "IN+_1") (pintype "bidirectional"))
    )
    (net (code "45") (name "VIN") (class "Default")
      (node (ref "S1") (pin "2") (pinfunction "P_2") (pintype "passive"))
      (node (ref "U$56") (pin "1") (pinfunction "+_1") (pintype "passive"))
    )
    (net (code "46") (name "V_BATT") (class "Default")
      (node (ref "C3") (pin "1") (pinfunction "1_1") (pintype "passive"))
      (node (ref "Q1") (pin "2") (pinfunction "S_2") (pintype "passive"))
      (node (ref "Q3") (pin "3") (pinfunction "D_3") (pintype "passive"))
      (node (ref "S1") (pin "1") (pinfunction "O_1") (pintype "passive"))
      (node (ref "U7") (pin "3") (pinfunction "VBAT_3") (pintype "power_in"))
    )
    (net (code "47") (name "V_USB") (class "Default")
      (node (ref "C8") (pin "2") (pinfunction "2_2") (pintype "passive"))
      (node (ref "CHG") (pin "A") (pinfunction "A_A") (pintype "passive"))
      (node (ref "D5") (pin "A") (pinfunction "A_A") (pintype "passive"))
      (node (ref "IC1") (pin "7") (pinfunction "REGIN_7") (pintype "power_in"))
      (node (ref "IC1") (pin "8") (pinfunction "VBUS_8") (pintype "power_in"))
      (node (ref "JP5") (pin "3") (pinfunction "3_3") (pintype "passive"))
      (node (ref "Q1") (pin "1") (pinfunction "G_1") (pintype "passive"))
      (node (ref "Q3") (pin "1") (pinfunction "G_1") (pintype "passive"))
      (node (ref "R9") (pin "2") (pinfunction "2_2") (pintype "passive"))
      (node (ref "U7") (pin "4") (pinfunction "VDD_4") (pintype "power_in"))
      (node (ref "X1") (pin "VBUS") (pinfunction "VBUS_VBUS") (pintype "power_in"))
    )
    (net (code "48") (name "XB_DTR") (class "Default")
      (node (ref "J1") (pin "1") (pinfunction "1_1") (pintype "passive"))
      (node (ref "U$2") (pin "DTR/SLEEP_RQ/DIO8") (pinfunction "DTR_DTR/SLEEP_RQ/DIO8") (pintype "bidirectional"))
    )
    (net (code "49") (name "XB_RTS") (class "Default")
      (node (ref "J1") (pin "2") (pinfunction "2_2") (pintype "passive"))
      (node (ref "U$2") (pin "RTS/DIO6") (pinfunction "RTS_RTS/DIO6") (pintype "bidirectional"))
    )
    (net (code "50") (name "unconnected-(IC1A-#RST-Pad9)") (class "Default")
      (node (ref "IC1") (pin "9") (pinfunction "#RST_9") (pintype "bidirectional"))
    )
    (net (code "51") (name "unconnected-(IC1A-#SUSPEND-Pad15)") (class "Default")
      (node (ref "IC1") (pin "15") (pinfunction "#SUSPEND_15") (pintype "output"))
    )
    (net (code "52") (name "unconnected-(IC1A-DCD-Pad24)") (class "Default")
      (node (ref "IC1") (pin "24") (pinfunction "DCD_24") (pintype "input"))
    )
    (net (code "53") (name "unconnected-(IC1A-DSR-Pad22)") (class "Default")
      (node (ref "IC1") (pin "22") (pinfunction "DSR_22") (pintype "input"))
    )
    (net (code "54") (name "unconnected-(IC1A-GPIO0{slash}TXLED-Pad14)") (class "Default")
      (node (ref "IC1") (pin "14") (pinfunction "GPIO0/TXLED_14") (pintype "bidirectional"))
    )
    (net (code "55") (name "unconnected-(IC1A-GPIO1{slash}RXLED-Pad13)") (class "Default")
      (node (ref "IC1") (pin "13") (pinfunction "GPIO1/RXLED_13") (pintype "bidirectional"))
    )
    (net (code "56") (name "unconnected-(IC1A-GPIO2-Pad12)") (class "Default")
      (node (ref "IC1") (pin "12") (pinfunction "GPIO2_12") (pintype "bidirectional"))
    )
    (net (code "57") (name "unconnected-(IC1A-GPIO3-Pad11)") (class "Default")
      (node (ref "IC1") (pin "11") (pinfunction "GPIO3_11") (pintype "bidirectional"))
    )
    (net (code "58") (name "unconnected-(IC1A-NC-Pad10)") (class "Default")
      (node (ref "IC1") (pin "10") (pinfunction "NC_10") (pintype "no_connect"))
    )
    (net (code "59") (name "unconnected-(IC1A-RI-Pad1)") (class "Default")
      (node (ref "IC1") (pin "1") (pinfunction "RI_1") (pintype "input"))
    )
    (net (code "60") (name "unconnected-(IC1A-RTS-Pad19)") (class "Default")
      (node (ref "IC1") (pin "19") (pinfunction "RTS_19") (pintype "output"))
    )
    (net (code "61") (name "unconnected-(IC1A-SUSPEND-Pad17)") (class "Default")
      (node (ref "IC1") (pin "17") (pinfunction "SUSPEND_17") (pintype "output"))
    )
    (net (code "62") (name "unconnected-(JP4-Pad5)") (class "Default")
      (node (ref "JP4") (pin "5") (pinfunction "5_5") (pintype "passive"))
    )
    (net (code "63") (name "unconnected-(JP4-Pad7)") (class "Default")
      (node (ref "JP4") (pin "7") (pinfunction "7_7") (pintype "passive"))
    )
    (net (code "64") (name "unconnected-(JP4-Pad8)") (class "Default")
      (node (ref "JP4") (pin "8") (pinfunction "8_8") (pintype "passive"))
    )
    (net (code "65") (name "unconnected-(JP4-Pad14)") (class "Default")
      (node (ref "JP4") (pin "14") (pinfunction "14_14") (pintype "passive"))
    )
    (net (code "66") (name "unconnected-(JP5-Pad2)") (class "Default")
      (node (ref "JP5") (pin "2") (pinfunction "2_2") (pintype "passive"))
    )
    (net (code "67") (name "unconnected-(JP5-Pad6)") (class "Default")
      (node (ref "JP5") (pin "6") (pinfunction "6_6") (pintype "passive"))
    )
    (net (code "68") (name "unconnected-(JP5-Pad9)") (class "Default")
      (node (ref "JP5") (pin "9") (pinfunction "9_9") (pintype "passive"))
    )
    (net (code "69") (name "unconnected-(JP5-Pad10)") (class "Default")
      (node (ref "JP5") (pin "10") (pinfunction "10_10") (pintype "passive"))
    )
    (net (code "70") (name "unconnected-(JP5-Pad11)") (class "Default")
      (node (ref "JP5") (pin "11") (pinfunction "11_11") (pintype "passive"))
    )
    (net (code "71") (name "unconnected-(S1-S-Pad3)") (class "Default")
      (node (ref "S1") (pin "3") (pinfunction "S_3") (pintype "passive"))
    )
    (net (code "72") (name "unconnected-(U6-P4-Pad4)") (class "Default")
      (node (ref "U6") (pin "4") (pinfunction "P4_4") (pintype "bidirectional"))
    )
    (net (code "73") (name "unconnected-(X1-PadID)") (class "Default")
      (node (ref "X1") (pin "ID") (pinfunction "ID_ID") (pintype "bidirectional"))
    )
  )
)
